# MotorController-BA6229.net
KiCad netlist of a schematic drawn in EAGLE
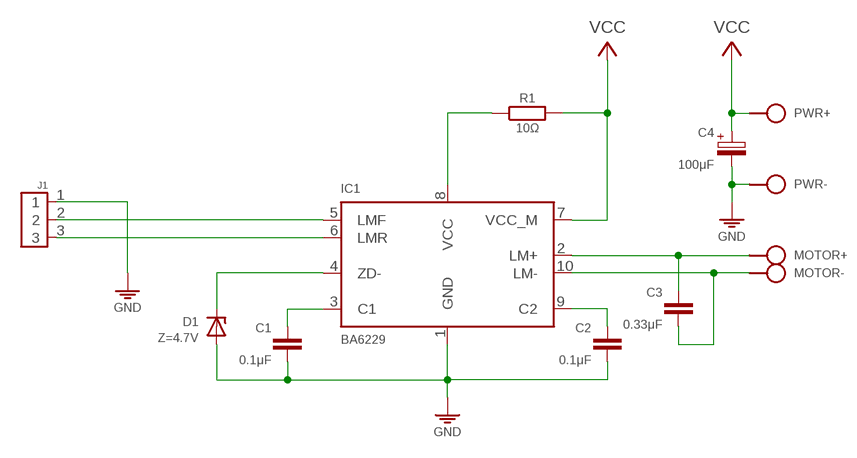
[diagram p0: schematic, sheet 1]

(export (version "E")
  (design (tool "Eeschema 10.0.6"))
  (components
    (comp (ref "C1")
      (value "0.1μF")
      (footprint "eagle-import:C050-020X044")
      (libsource (lib "eagle-import") (part "C050-020X044"))
    )
    (comp (ref "C2")
      (value "0.1μF")
      (footprint "eagle-import:C050-020X044")
      (libsource (lib "eagle-import") (part "C050-020X044"))
    )
    (comp (ref "C3")
      (value "0.33μF")
      (footprint "eagle-import:C050-020X044")
      (libsource (lib "eagle-import") (part "C050-020X044"))
    )
    (comp (ref "C4")
      (value "100μF")
      (footprint "eagle-import:E5-5_V")
      (libsource (lib "eagle-import") (part "CPOLE5-5/V"))
    )
    (comp (ref "D1")
      (value "Z=4.7V")
      (footprint "eagle-import:DO34Z7V")
      (libsource (lib "eagle-import") (part "Z-DIODE34Z7V"))
    )
    (comp (ref "IC1")
      (value "BA6229")
      (footprint "eagle-import:SIL10")
      (libsource (lib "eagle-import") (part "BA6229"))
    )
    (comp (ref "J1")
      (value "CONN-3P-3P")
      (footprint "eagle-import:CONN-3P")
      (libsource (lib "eagle-import") (part "CONN-3P-3P"))
    )
    (comp (ref "MOTOR+")
      (value "SPAD")
      (footprint "eagle-import:SPAD")
      (libsource (lib "eagle-import") (part "SPAD"))
    )
    (comp (ref "MOTOR-")
      (value "SPAD")
      (footprint "eagle-import:SPAD")
      (libsource (lib "eagle-import") (part "SPAD"))
    )
    (comp (ref "PWR+")
      (value "SPAD")
      (footprint "eagle-import:SPAD")
      (libsource (lib "eagle-import") (part "SPAD"))
    )
    (comp (ref "PWR-")
      (value "SPAD")
      (footprint "eagle-import:SPAD")
      (libsource (lib "eagle-import") (part "SPAD"))
    )
    (comp (ref "R1")
      (value "10Ω")
      (footprint "eagle-import:0204_10-V")
      (libsource (lib "eagle-import") (part "R-H0204/10-V"))
    )
  )
  (nets
    (net (code "1") (name "GND") (class "Default")
      (node (ref "C1") (pin "2") (pinfunction "2_2") (pintype "passive"))
      (node (ref "C2") (pin "2") (pinfunction "2_2") (pintype "passive"))
      (node (ref "C4") (pin "-") (pinfunction "-_-") (pintype "passive"))
      (node (ref "D1") (pin "A") (pinfunction "A_A") (pintype "passive"))
      (node (ref "IC1") (pin "1") (pinfunction "GND_1") (pintype "bidirectional"))
      (node (ref "J1") (pin "1") (pinfunction "1_1") (pintype "bidirectional"))
      (node (ref "PWR-") (pin "1") (pinfunction "P$1_1") (pintype "passive"))
    )
    (net (code "2") (name "Net-(IC1-C1)") (class "Default")
      (node (ref "C1") (pin "1") (pinfunction "1_1") (pintype "passive"))
      (node (ref "IC1") (pin "3") (pinfunction "C1_3") (pintype "bidirectional"))
    )
    (net (code "3") (name "Net-(IC1-C2)") (class "Default")
      (node (ref "C2") (pin "1") (pinfunction "1_1") (pintype "passive"))
      (node (ref "IC1") (pin "9") (pinfunction "C2_9") (pintype "bidirectional"))
    )
    (net (code "4") (name "Net-(IC1-LM+)") (class "Default")
      (node (ref "C3") (pin "1") (pinfunction "1_1") (pintype "passive"))
      (node (ref "IC1") (pin "2") (pinfunction "LM+_2") (pintype "bidirectional"))
      (node (ref "MOTOR+") (pin "1") (pinfunction "P$1_1") (pintype "passive"))
    )
    (net (code "5") (name "Net-(IC1-LM-)") (class "Default")
      (node (ref "C3") (pin "2") (pinfunction "2_2") (pintype "passive"))
      (node (ref "IC1") (pin "10") (pinfunction "LM-_10") (pintype "bidirectional"))
      (node (ref "MOTOR-") (pin "1") (pinfunction "P$1_1") (pintype "passive"))
    )
    (net (code "6") (name "Net-(IC1-LMF)") (class "Default")
      (node (ref "IC1") (pin "5") (pinfunction "LMF_5") (pintype "bidirectional"))
      (node (ref "J1") (pin "2") (pinfunction "2_2") (pintype "bidirectional"))
    )
    (net (code "7") (name "Net-(IC1-LMR)") (class "Default")
      (node (ref "IC1") (pin "6") (pinfunction "LMR_6") (pintype "bidirectional"))
      (node (ref "J1") (pin "3") (pinfunction "3_3") (pintype "bidirectional"))
    )
    (net (code "8") (name "Net-(IC1-VCC)") (class "Default")
      (node (ref "IC1") (pin "8") (pinfunction "VCC_8") (pintype "bidirectional"))
      (node (ref "R1") (pin "1") (pinfunction "1_1") (pintype "passive"))
    )
    (net (code "9") (name "Net-(IC1-ZD-)") (class "Default")
      (node (ref "D1") (pin "C") (pinfunction "C_C") (pintype "passive"))
      (node (ref "IC1") (pin "4") (pinfunction "ZD-_4") (pintype "bidirectional"))
    )
    (net (code "10") (name "VCC") (class "Default")
      (node (ref "C4") (pin "+") (pinfunction "+_+") (pintype "passive"))
      (node (ref "IC1") (pin "7") (pinfunction "VCC_M_7") (pintype "bidirectional"))
      (node (ref "PWR+") (pin "1") (pinfunction "P$1_1") (pintype "passive"))
      (node (ref "R1") (pin "2") (pinfunction "2_2") (pintype "passive"))
    )
  )
)
